# senseBox-VEML-TSL_v20.net
KiCad netlist of a schematic drawn in EAGLE
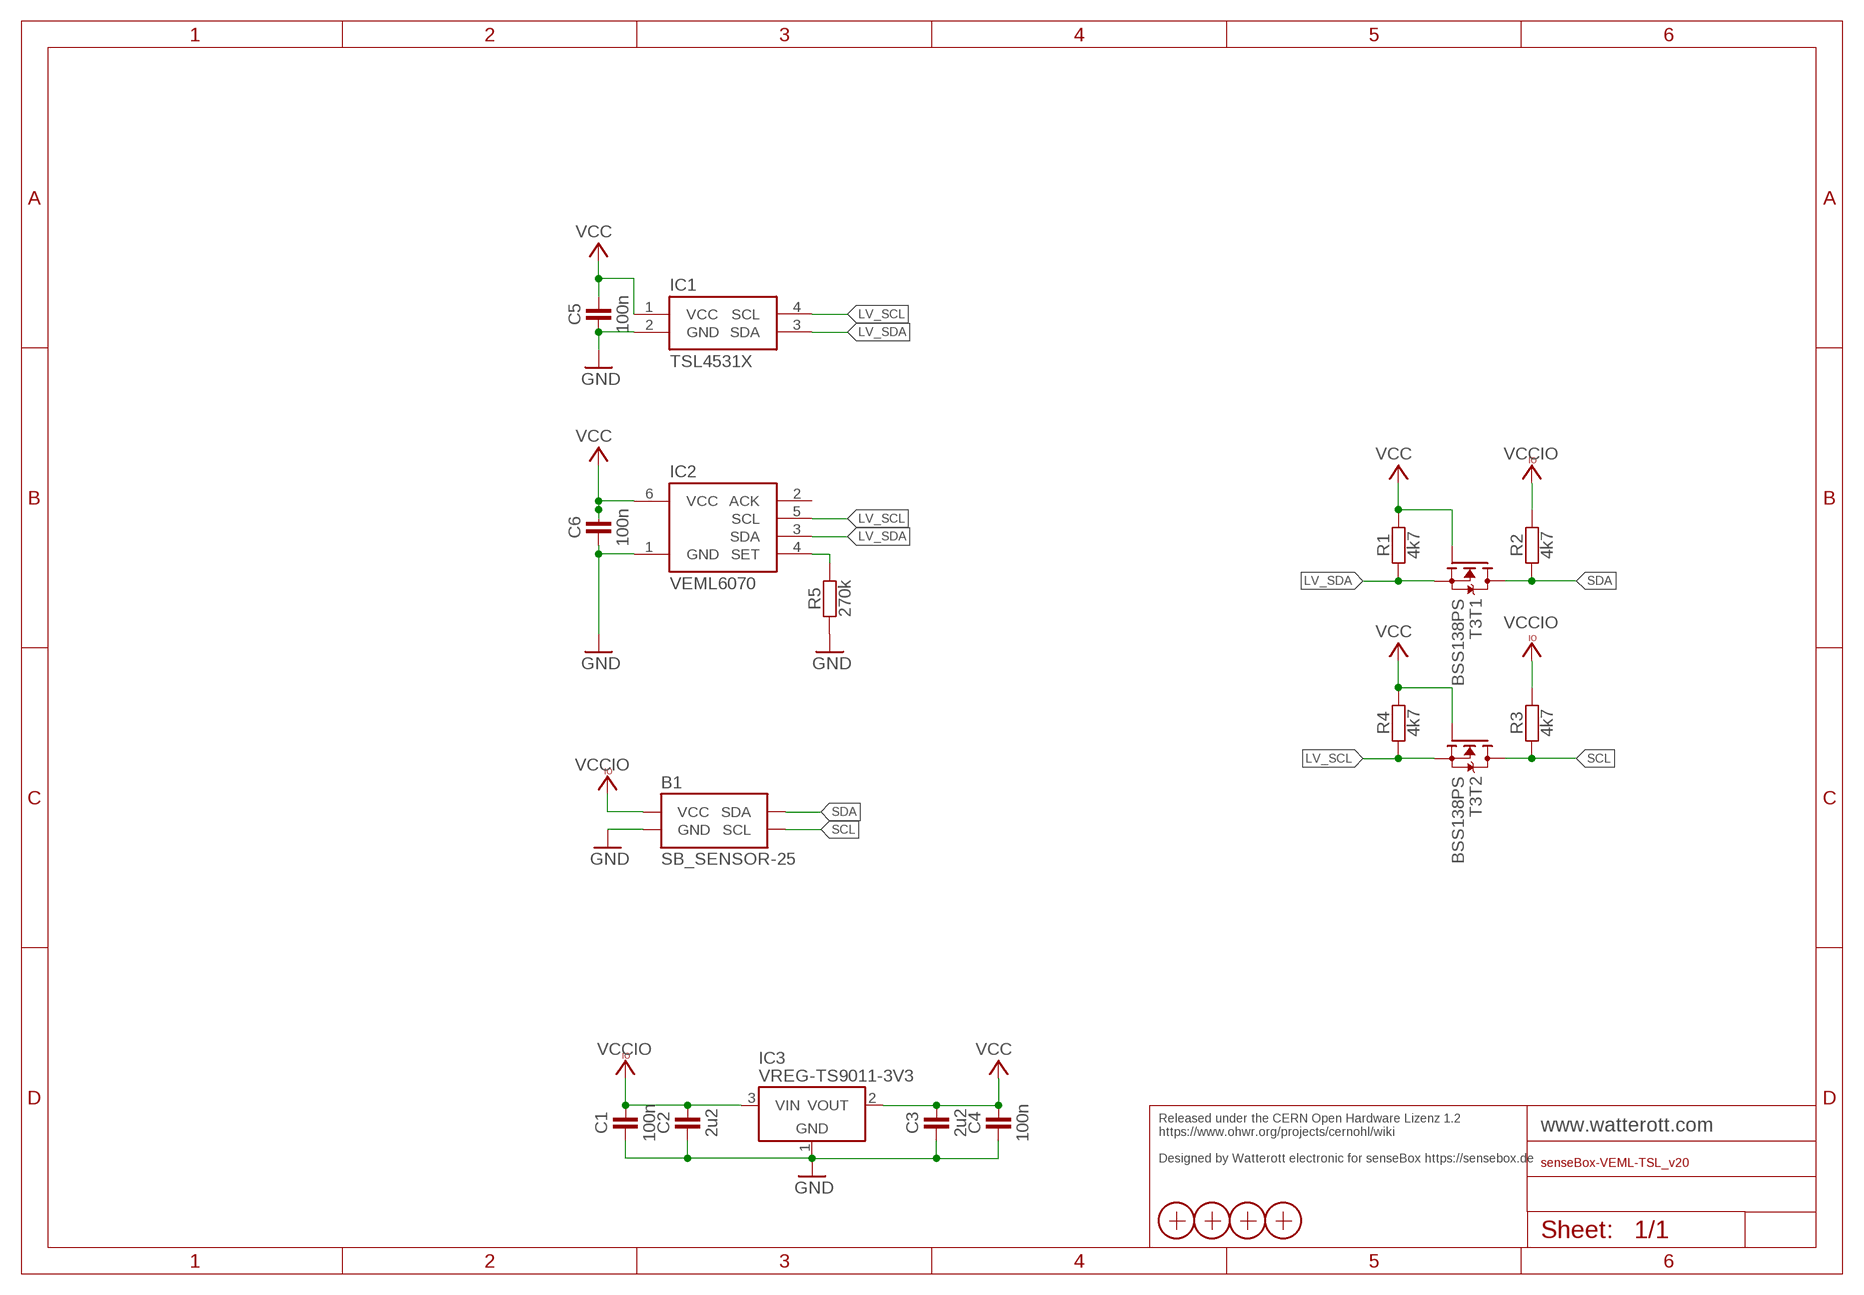
[diagram p0: schematic, sheet 1]

(export (version "E")
  (design (tool "Eeschema 10.0.6"))
  (components
    (comp (ref "B1")
      (value "SB_SENSOR-25")
      (footprint "eagle-import:SB-25X25")
      (libsource (lib "eagle-import") (part "SB_SENSOR-25"))
    )
    (comp (ref "C1")
      (value "100n")
      (footprint "eagle-import:C0402")
      (libsource (lib "eagle-import") (part "CAPACITOR-0402"))
    )
    (comp (ref "C2")
      (value "2u2")
      (footprint "eagle-import:C0402")
      (libsource (lib "eagle-import") (part "CAPACITOR-0402"))
    )
    (comp (ref "C3")
      (value "2u2")
      (footprint "eagle-import:C0402")
      (libsource (lib "eagle-import") (part "CAPACITOR-0402"))
    )
    (comp (ref "C4")
      (value "100n")
      (footprint "eagle-import:C0402")
      (libsource (lib "eagle-import") (part "CAPACITOR-0402"))
    )
    (comp (ref "C5")
      (value "100n")
      (footprint "eagle-import:C0402")
      (libsource (lib "eagle-import") (part "CAPACITOR-0402"))
    )
    (comp (ref "C6")
      (value "100n")
      (footprint "eagle-import:C0402")
      (libsource (lib "eagle-import") (part "CAPACITOR-0402"))
    )
    (comp (ref "IC1")
      (value "TSL4531X")
      (footprint "eagle-import:AMS_CL")
      (libsource (lib "eagle-import") (part "TSL4531X"))
    )
    (comp (ref "IC2")
      (value "VEML6070")
      (footprint "eagle-import:OPLGA")
      (libsource (lib "eagle-import") (part "VEML6070"))
    )
    (comp (ref "IC3")
      (value "VREG-TS9011-3V3")
      (footprint "eagle-import:SOT23")
      (libsource (lib "eagle-import") (part "VREG-TS9011-3V3"))
    )
    (comp (ref "R1")
      (value "4k7")
      (footprint "eagle-import:C0402")
      (libsource (lib "eagle-import") (part "RESISTOR-0402"))
    )
    (comp (ref "R2")
      (value "4k7")
      (footprint "eagle-import:C0402")
      (libsource (lib "eagle-import") (part "RESISTOR-0402"))
    )
    (comp (ref "R3")
      (value "4k7")
      (footprint "eagle-import:C0402")
      (libsource (lib "eagle-import") (part "RESISTOR-0402"))
    )
    (comp (ref "R4")
      (value "4k7")
      (footprint "eagle-import:C0402")
      (libsource (lib "eagle-import") (part "RESISTOR-0402"))
    )
    (comp (ref "R5")
      (value "270k")
      (footprint "eagle-import:C0402")
      (libsource (lib "eagle-import") (part "RESISTOR-0402"))
    )
    (comp (ref "T3")
      (value "BSS138PS")
      (footprint "eagle-import:SOT363")
      (libsource (lib "eagle-import") (part "BSS138PS"))
    )
    (comp (ref "X1")
      (value "PASSER-07")
      (footprint "eagle-import:PASSER_07MM")
      (libsource (lib "eagle-import") (part "PASSER-07"))
    )
    (comp (ref "X2")
      (value "PASSER-07")
      (footprint "eagle-import:PASSER_07MM")
      (libsource (lib "eagle-import") (part "PASSER-07"))
    )
    (comp (ref "X3")
      (value "PASSER-07")
      (footprint "eagle-import:PASSER_07MM")
      (libsource (lib "eagle-import") (part "PASSER-07"))
    )
    (comp (ref "X4")
      (value "PASSER-07")
      (footprint "eagle-import:PASSER_07MM")
      (libsource (lib "eagle-import") (part "PASSER-07"))
    )
  )
  (nets
    (net (code "1") (name "GND") (class "Default")
      (node (ref "B1") (pin "GND") (pinfunction "GND_GND") (pintype "power_in"))
      (node (ref "C1") (pin "1") (pinfunction "1_1") (pintype "passive"))
      (node (ref "C2") (pin "1") (pinfunction "1_1") (pintype "passive"))
      (node (ref "C3") (pin "1") (pinfunction "1_1") (pintype "passive"))
      (node (ref "C4") (pin "1") (pinfunction "1_1") (pintype "passive"))
      (node (ref "C5") (pin "1") (pinfunction "1_1") (pintype "passive"))
      (node (ref "C6") (pin "1") (pinfunction "1_1") (pintype "passive"))
      (node (ref "IC1") (pin "2") (pinfunction "GND_2") (pintype "power_in"))
      (node (ref "IC2") (pin "1") (pinfunction "GND_1") (pintype "power_in"))
      (node (ref "IC3") (pin "1") (pinfunction "GND_1") (pintype "power_in"))
      (node (ref "R5") (pin "1") (pinfunction "1_1") (pintype "passive"))
    )
    (net (code "2") (name "LV_SCL") (class "Default")
      (node (ref "IC1") (pin "4") (pinfunction "SCL_4") (pintype "bidirectional"))
      (node (ref "IC2") (pin "5") (pinfunction "SCL_5") (pintype "bidirectional"))
      (node (ref "R4") (pin "1") (pinfunction "1_1") (pintype "passive"))
      (node (ref "T3") (pin "4") (pinfunction "S_4") (pintype "passive"))
    )
    (net (code "3") (name "LV_SDA") (class "Default")
      (node (ref "IC1") (pin "3") (pinfunction "SDA_3") (pintype "bidirectional"))
      (node (ref "IC2") (pin "3") (pinfunction "SDA_3") (pintype "bidirectional"))
      (node (ref "R1") (pin "1") (pinfunction "1_1") (pintype "passive"))
      (node (ref "T3") (pin "1") (pinfunction "S_1") (pintype "passive"))
    )
    (net (code "4") (name "Net-(IC2-SET)") (class "Default")
      (node (ref "IC2") (pin "4") (pinfunction "SET_4") (pintype "bidirectional"))
      (node (ref "R5") (pin "2") (pinfunction "2_2") (pintype "passive"))
    )
    (net (code "5") (name "SCL") (class "Default")
      (node (ref "B1") (pin "SCL") (pinfunction "SCL_SCL") (pintype "bidirectional"))
      (node (ref "R3") (pin "1") (pinfunction "1_1") (pintype "passive"))
      (node (ref "T3") (pin "3") (pinfunction "D_3") (pintype "passive"))
    )
    (net (code "6") (name "SDA") (class "Default")
      (node (ref "B1") (pin "SDA") (pinfunction "SDA_SDA") (pintype "bidirectional"))
      (node (ref "R2") (pin "1") (pinfunction "1_1") (pintype "passive"))
      (node (ref "T3") (pin "6") (pinfunction "D_6") (pintype "passive"))
    )
    (net (code "7") (name "VCC") (class "Default")
      (node (ref "C3") (pin "2") (pinfunction "2_2") (pintype "passive"))
      (node (ref "C4") (pin "2") (pinfunction "2_2") (pintype "passive"))
      (node (ref "C5") (pin "2") (pinfunction "2_2") (pintype "passive"))
      (node (ref "C6") (pin "2") (pinfunction "2_2") (pintype "passive"))
      (node (ref "IC1") (pin "1") (pinfunction "VCC_1") (pintype "power_in"))
      (node (ref "IC2") (pin "6") (pinfunction "VCC_6") (pintype "power_in"))
      (node (ref "IC3") (pin "2") (pinfunction "VOUT_2") (pintype "power_in"))
      (node (ref "R1") (pin "2") (pinfunction "2_2") (pintype "passive"))
      (node (ref "R4") (pin "2") (pinfunction "2_2") (pintype "passive"))
      (node (ref "T3") (pin "2") (pinfunction "G_2") (pintype "passive"))
      (node (ref "T3") (pin "5") (pinfunction "G_5") (pintype "passive"))
    )
    (net (code "8") (name "VCCIO") (class "Default")
      (node (ref "B1") (pin "VCC") (pinfunction "VCC_VCC") (pintype "power_in"))
      (node (ref "C1") (pin "2") (pinfunction "2_2") (pintype "passive"))
      (node (ref "C2") (pin "2") (pinfunction "2_2") (pintype "passive"))
      (node (ref "IC3") (pin "3") (pinfunction "VIN_3") (pintype "power_in"))
      (node (ref "R2") (pin "2") (pinfunction "2_2") (pintype "passive"))
      (node (ref "R3") (pin "2") (pinfunction "2_2") (pintype "passive"))
    )
    (net (code "9") (name "unconnected-(IC2-ACK-Pad2)") (class "Default")
      (node (ref "IC2") (pin "2") (pinfunction "ACK_2") (pintype "bidirectional"))
    )
  )
)
